# Light_Barrier_2015_3.net
KiCad netlist of a schematic drawn in EAGLE
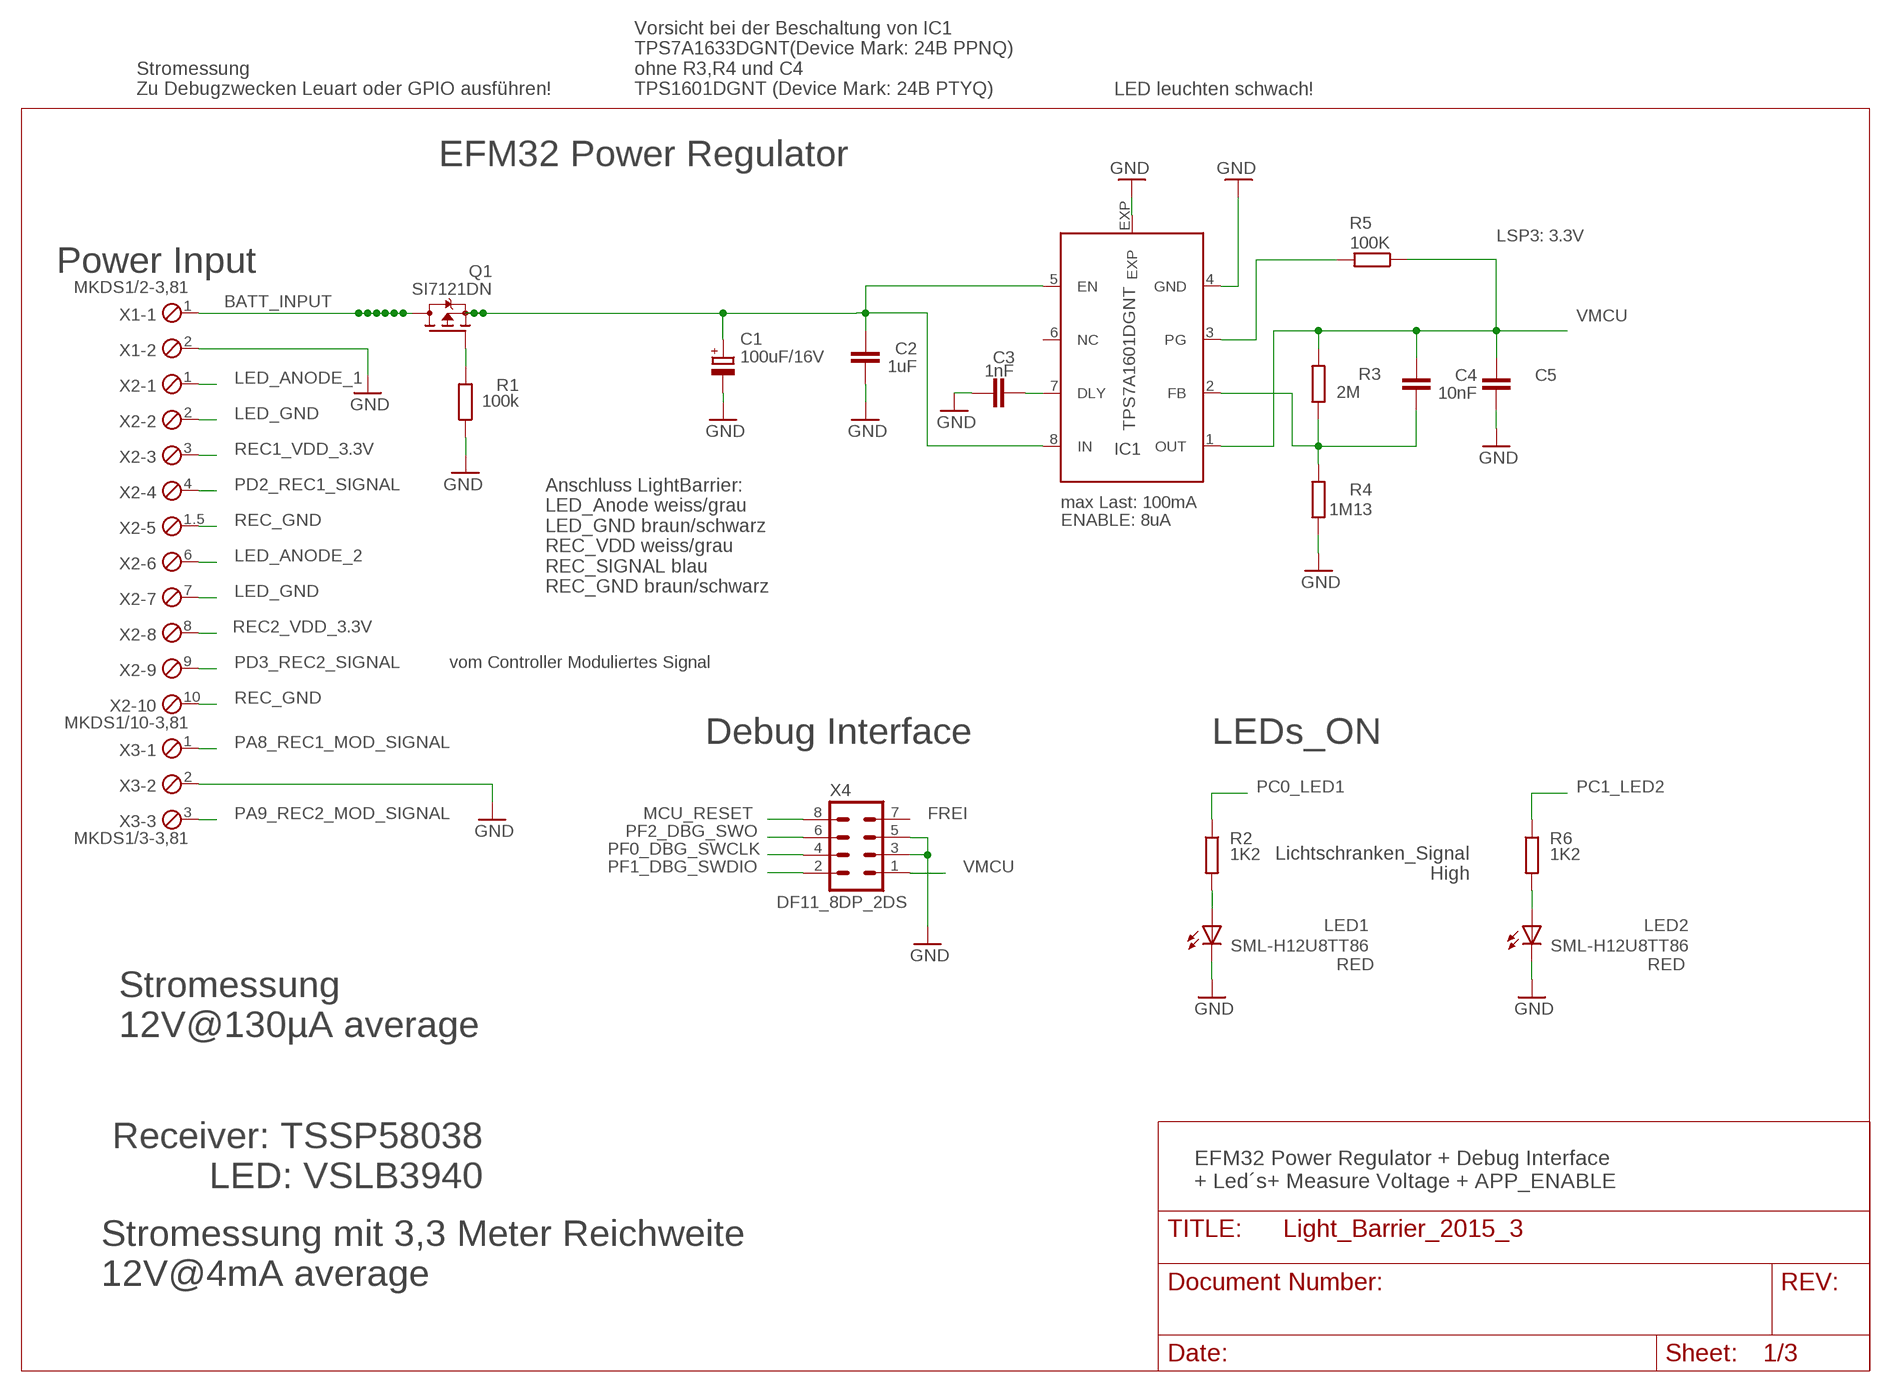
[diagram p0: schematic, sheet 1]
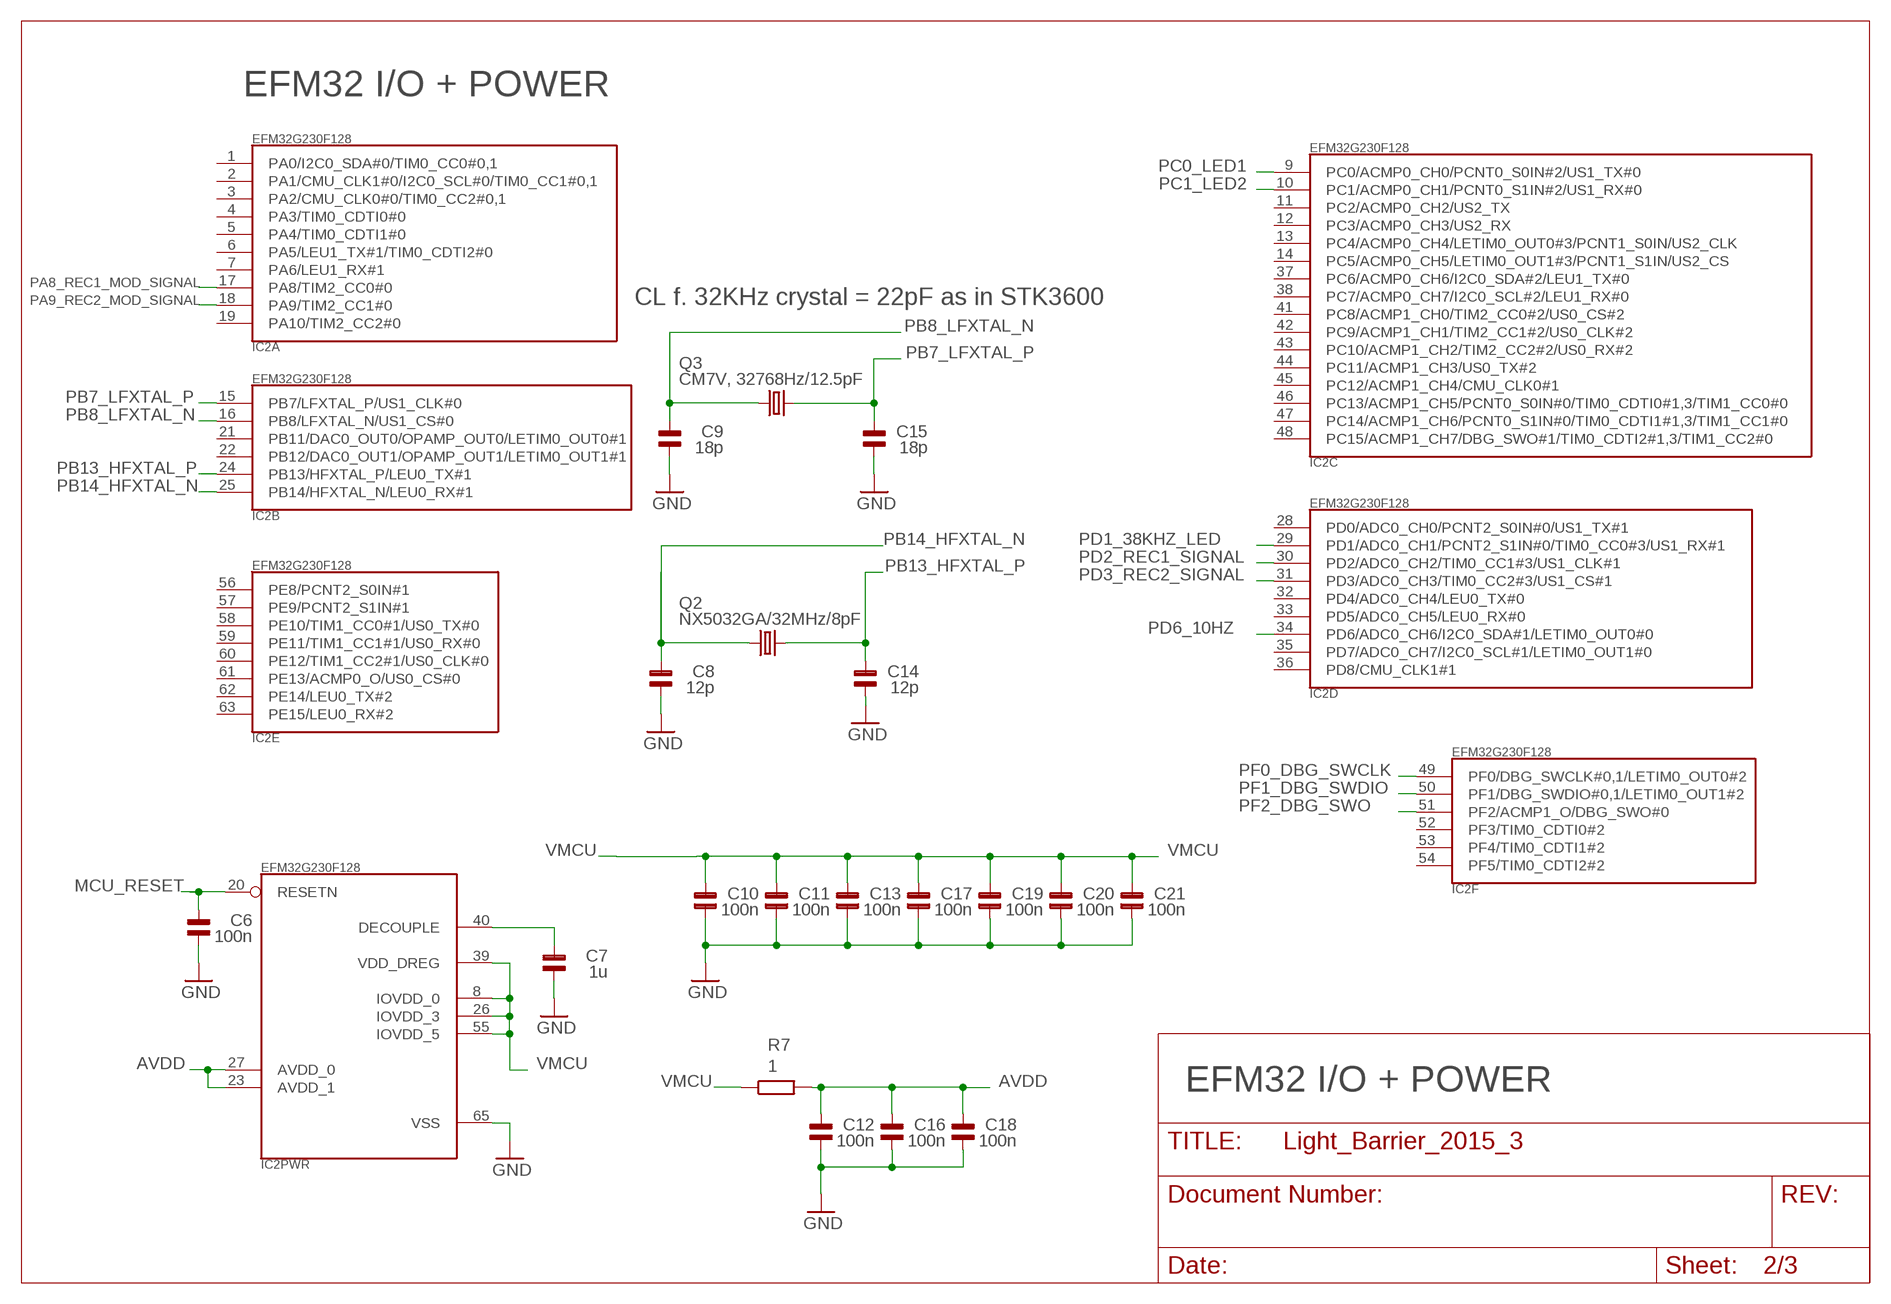
[diagram p1: schematic, sheet 2]
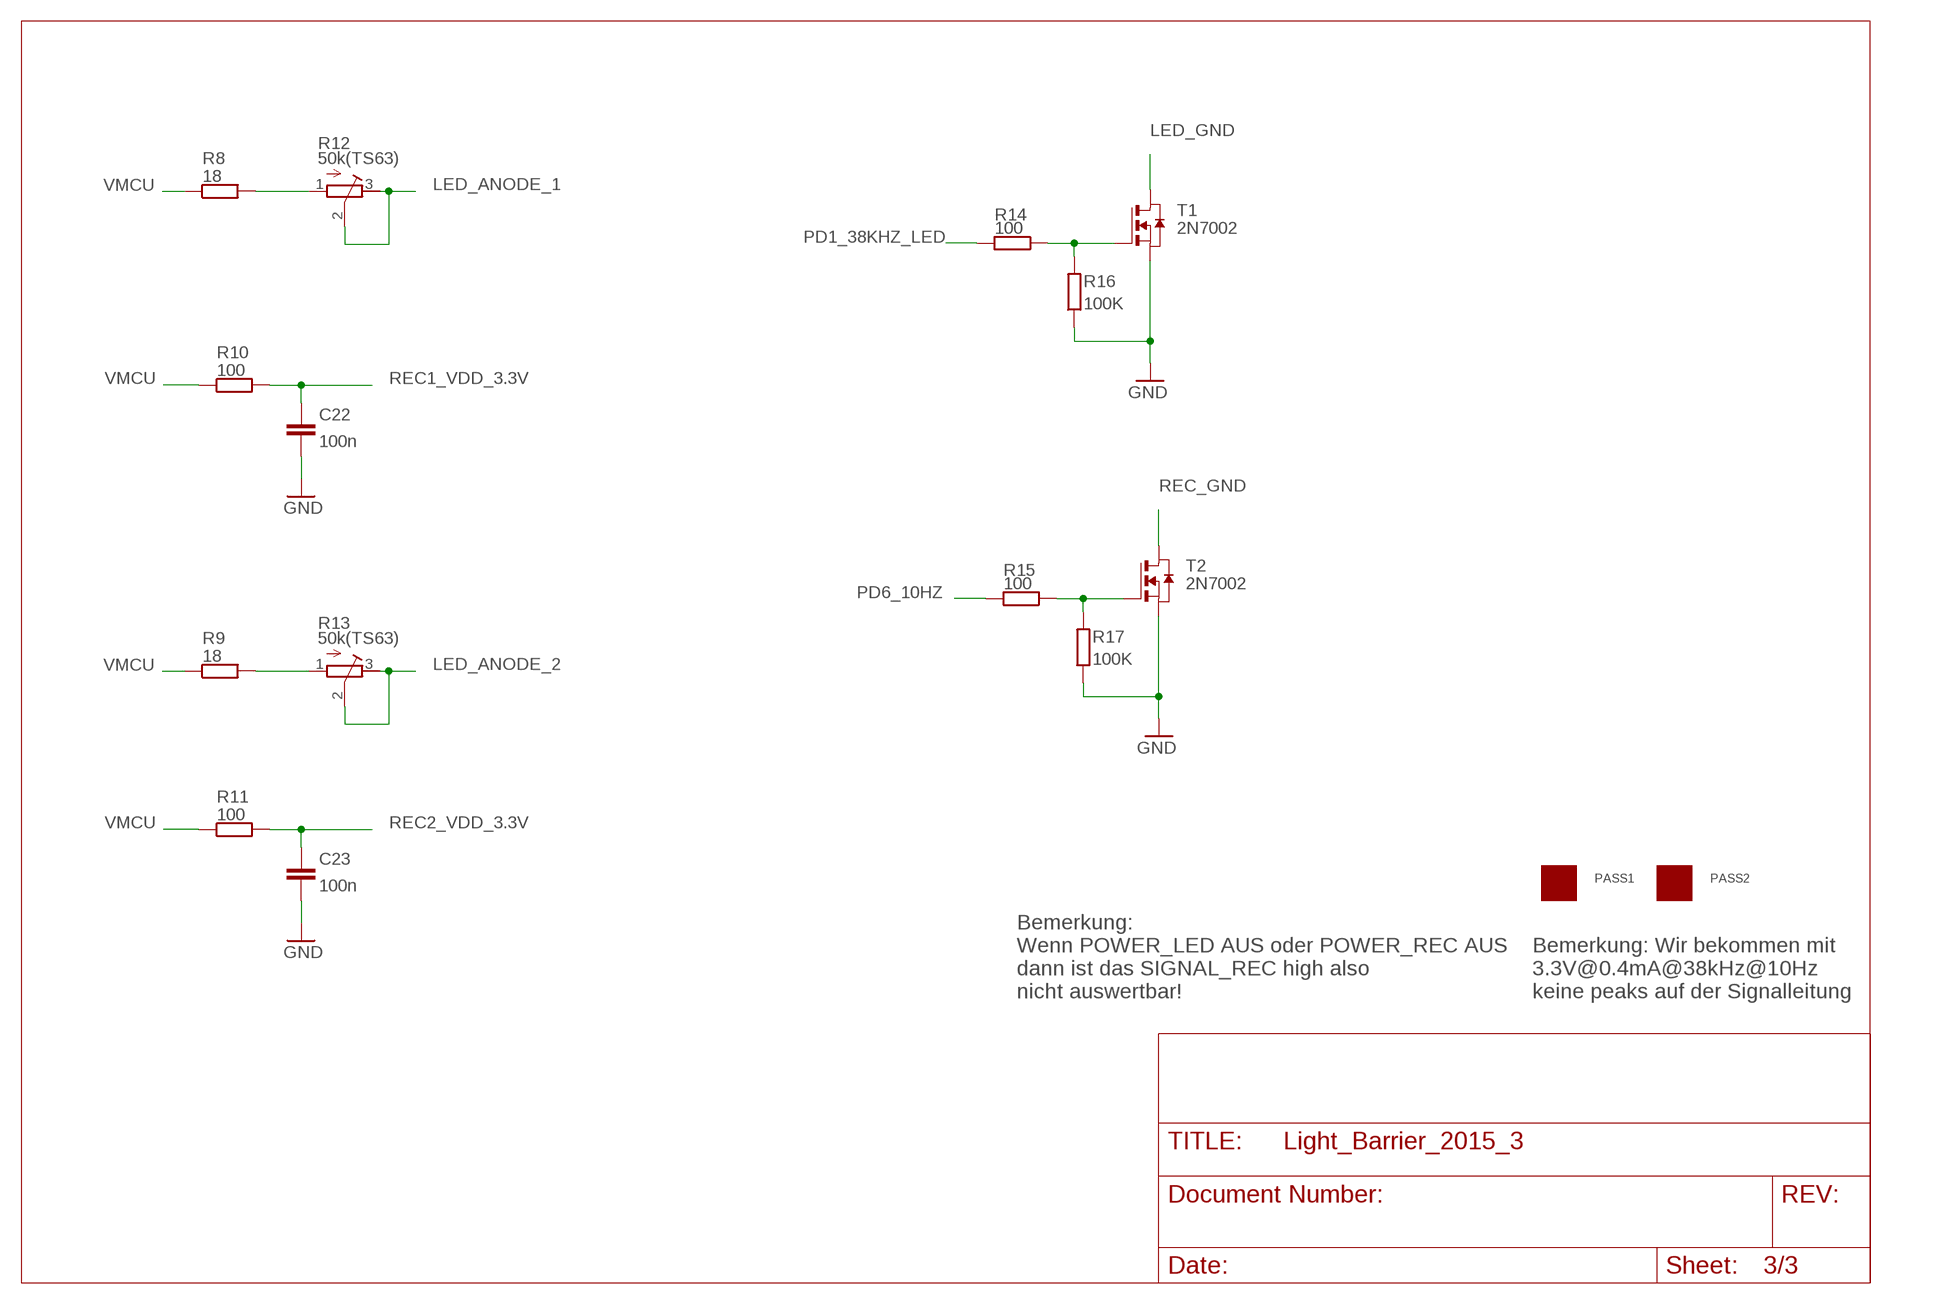
[diagram p2: schematic, sheet 3]

(export (version "E")
  (design (tool "Eeschema 10.0.6"))
  (components
    (comp (ref "C6")
      (value "100n")
      (footprint "eagle-import:0805")
      (libsource (lib "eagle-import") (part "C_SMD0805"))
    )
    (comp (ref "C7")
      (value "1u")
      (footprint "eagle-import:0805")
      (libsource (lib "eagle-import") (part "C_SMD0805"))
    )
    (comp (ref "C8")
      (value "12p")
      (footprint "eagle-import:0805")
      (libsource (lib "eagle-import") (part "C_SMD0805"))
    )
    (comp (ref "C9")
      (value "18p")
      (footprint "eagle-import:0805")
      (libsource (lib "eagle-import") (part "C_SMD0805"))
    )
    (comp (ref "C10")
      (value "100n")
      (footprint "eagle-import:0805")
      (libsource (lib "eagle-import") (part "C_SMD0805"))
    )
    (comp (ref "C11")
      (value "100n")
      (footprint "eagle-import:0805")
      (libsource (lib "eagle-import") (part "C_SMD0805"))
    )
    (comp (ref "C12")
      (value "100n")
      (footprint "eagle-import:0805")
      (libsource (lib "eagle-import") (part "C_SMD0805"))
    )
    (comp (ref "C13")
      (value "100n")
      (footprint "eagle-import:0805")
      (libsource (lib "eagle-import") (part "C_SMD0805"))
    )
    (comp (ref "C14")
      (value "12p")
      (footprint "eagle-import:0805")
      (libsource (lib "eagle-import") (part "C_SMD0805"))
    )
    (comp (ref "C15")
      (value "18p")
      (footprint "eagle-import:0805")
      (libsource (lib "eagle-import") (part "C_SMD0805"))
    )
    (comp (ref "C16")
      (value "100n")
      (footprint "eagle-import:0805")
      (libsource (lib "eagle-import") (part "C_SMD0805"))
    )
    (comp (ref "C17")
      (value "100n")
      (footprint "eagle-import:0805")
      (libsource (lib "eagle-import") (part "C_SMD0805"))
    )
    (comp (ref "C18")
      (value "100n")
      (footprint "eagle-import:0805")
      (libsource (lib "eagle-import") (part "C_SMD0805"))
    )
    (comp (ref "C19")
      (value "100n")
      (footprint "eagle-import:0805")
      (libsource (lib "eagle-import") (part "C_SMD0805"))
    )
    (comp (ref "C20")
      (value "100n")
      (footprint "eagle-import:0805")
      (libsource (lib "eagle-import") (part "C_SMD0805"))
    )
    (comp (ref "C21")
      (value "100n")
      (footprint "eagle-import:0805")
      (libsource (lib "eagle-import") (part "C_SMD0805"))
    )
    (comp (ref "IC2")
      (value "EFM32G230F128")
      (footprint "eagle-import:QFN64")
      (libsource (lib "eagle-import") (part "EFM32G230F128"))
    )
    (comp (ref "Q2")
      (value "NX5032GA/32MHz/8pF")
      (footprint "eagle-import:CRYSTAL2P5.0X3.2")
      (libsource (lib "eagle-import") (part "CRYSTAL2P5.0X3.2"))
    )
    (comp (ref "Q3")
      (value "CM7V, 32768Hz/12.5pF")
      (footprint "eagle-import:CRYSTAL2P3.2X1.5")
      (libsource (lib "eagle-import") (part "CRYSTAL2P"))
    )
    (comp (ref "R7")
      (value "1")
      (footprint "eagle-import:R0805")
      (libsource (lib "eagle-import") (part "R-EU_R0805"))
    )
    (comp (ref "C22")
      (value "100n")
      (footprint "eagle-import:C0805")
      (libsource (lib "eagle-import") (part "C-EUC0805"))
    )
    (comp (ref "C23")
      (value "100n")
      (footprint "eagle-import:C0805")
      (libsource (lib "eagle-import") (part "C-EUC0805"))
    )
    (comp (ref "PASS1")
      (value "ROUND_1MM1.5")
      (footprint "eagle-import:ROUND2_1.5MM")
      (libsource (lib "eagle-import") (part "ROUND_1MM1.5"))
    )
    (comp (ref "PASS2")
      (value "ROUND_1MM1.5")
      (footprint "eagle-import:ROUND2_1.5MM")
      (libsource (lib "eagle-import") (part "ROUND_1MM1.5"))
    )
    (comp (ref "R8")
      (value "18")
      (footprint "eagle-import:R0805")
      (libsource (lib "eagle-import") (part "R-EU_R0805"))
    )
    (comp (ref "R9")
      (value "18")
      (footprint "eagle-import:R0805")
      (libsource (lib "eagle-import") (part "R-EU_R0805"))
    )
    (comp (ref "R10")
      (value "100")
      (footprint "eagle-import:R0805")
      (libsource (lib "eagle-import") (part "R-EU_R0805"))
    )
    (comp (ref "R11")
      (value "100")
      (footprint "eagle-import:R0805")
      (libsource (lib "eagle-import") (part "R-EU_R0805"))
    )
    (comp (ref "R12")
      (value "50k(TS63)")
      (footprint "eagle-import:RTRIMTS63Y")
      (libsource (lib "eagle-import") (part "R-TRIMMTS63Y"))
    )
    (comp (ref "R13")
      (value "50k(TS63)")
      (footprint "eagle-import:RTRIMTS63Y")
      (libsource (lib "eagle-import") (part "R-TRIMMTS63Y"))
    )
    (comp (ref "R14")
      (value "100")
      (footprint "eagle-import:R0805")
      (libsource (lib "eagle-import") (part "resistor_R-EU_R0805"))
    )
    (comp (ref "R15")
      (value "100")
      (footprint "eagle-import:R0805")
      (libsource (lib "eagle-import") (part "resistor_R-EU_R0805"))
    )
    (comp (ref "R16")
      (value "100K")
      (footprint "eagle-import:R0805")
      (libsource (lib "eagle-import") (part "resistor_R-EU_R0805"))
    )
    (comp (ref "R17")
      (value "100K")
      (footprint "eagle-import:R0805")
      (libsource (lib "eagle-import") (part "resistor_R-EU_R0805"))
    )
    (comp (ref "T1")
      (value "2N7002")
      (footprint "eagle-import:ZETEX_SOT-23")
      (libsource (lib "eagle-import") (part "ZETEX_NMOSSOT23"))
    )
    (comp (ref "T2")
      (value "2N7002")
      (footprint "eagle-import:ZETEX_SOT-23")
      (libsource (lib "eagle-import") (part "ZETEX_NMOSSOT23"))
    )
    (comp (ref "C1")
      (value "100uF/16V")
      (footprint "eagle-import:PANASONIC_E")
      (libsource (lib "eagle-import") (part "CPOL-EUE"))
    )
    (comp (ref "C2")
      (value "1uF")
      (footprint "eagle-import:C0603")
      (libsource (lib "eagle-import") (part "resistor_C-EUC0603"))
    )
    (comp (ref "C3")
      (value "1nF")
      (footprint "eagle-import:C0603")
      (libsource (lib "eagle-import") (part "resistor_C-EUC0603"))
    )
    (comp (ref "C4")
      (value "10nF")
      (footprint "eagle-import:C0603")
      (libsource (lib "eagle-import") (part "resistor_C-EUC0603"))
    )
    (comp (ref "C5")
      (value "10uF")
      (footprint "eagle-import:C1206")
      (libsource (lib "eagle-import") (part "resistor_C-EUC1206"))
    )
    (comp (ref "IC1")
      (value "TPS7A1601DGNT")
      (footprint "eagle-import:DGN_S-PDSO-G8-EXP")
      (libsource (lib "eagle-import") (part "TPS7A16"))
    )
    (comp (ref "LED1")
      (value "SML-H12U8TT86")
      (footprint "eagle-import:CHIPLED_0805")
      (libsource (lib "eagle-import") (part "LEDCHIPLED_0805"))
    )
    (comp (ref "LED2")
      (value "SML-H12U8TT86")
      (footprint "eagle-import:CHIPLED_0805")
      (libsource (lib "eagle-import") (part "LEDCHIPLED_0805"))
    )
    (comp (ref "Q1")
      (value "SI7121DN")
      (footprint "eagle-import:TRANSISTOR-FET_1212-8S")
      (libsource (lib "eagle-import") (part "TRANSISTOR-FET_SI7113DN"))
    )
    (comp (ref "R1")
      (value "100k")
      (footprint "eagle-import:R0805")
      (libsource (lib "eagle-import") (part "resistor_R-EU_R0805"))
    )
    (comp (ref "R2")
      (value "1K2")
      (footprint "eagle-import:R0805")
      (libsource (lib "eagle-import") (part "resistor_R-EU_R0805"))
    )
    (comp (ref "R3")
      (value "2M")
      (footprint "eagle-import:R0805")
      (libsource (lib "eagle-import") (part "resistor_R-EU_R0805"))
    )
    (comp (ref "R4")
      (value "1M13")
      (footprint "eagle-import:R0805")
      (libsource (lib "eagle-import") (part "resistor_R-EU_R0805"))
    )
    (comp (ref "R5")
      (value "100K")
      (footprint "eagle-import:R0805")
      (libsource (lib "eagle-import") (part "resistor_R-EU_R0805"))
    )
    (comp (ref "R6")
      (value "1K2")
      (footprint "eagle-import:R0805")
      (libsource (lib "eagle-import") (part "resistor_R-EU_R0805"))
    )
    (comp (ref "X1")
      (value "MKDS1/2-3,81")
      (footprint "eagle-import:2POL381")
      (libsource (lib "eagle-import") (part "MKDS1/2-3,81"))
    )
    (comp (ref "X2")
      (value "MKDS1/10-3,81")
      (footprint "eagle-import:10POL381")
      (libsource (lib "eagle-import") (part "MKDS1/10-3,81"))
    )
    (comp (ref "X3")
      (value "MKDS1/3-3,81")
      (footprint "eagle-import:3POL381")
      (libsource (lib "eagle-import") (part "MKDS1/3-3,81"))
    )
    (comp (ref "X4")
      (value "DF11_8DP_2DS")
      (footprint "eagle-import:DP11_8DP-2DS")
      (libsource (lib "eagle-import") (part "DP11_8DP_2DS"))
    )
  )
  (nets
    (net (code "1") (name "AVDD") (class "Default")
      (node (ref "C12") (pin "2") (pinfunction "2_2") (pintype "passive"))
      (node (ref "C16") (pin "2") (pinfunction "2_2") (pintype "passive"))
      (node (ref "C18") (pin "2") (pinfunction "2_2") (pintype "passive"))
      (node (ref "IC2") (pin "23") (pinfunction "AVDD_1_23") (pintype "power_in"))
      (node (ref "IC2") (pin "27") (pinfunction "AVDD_0_27") (pintype "power_in"))
      (node (ref "R7") (pin "2") (pinfunction "2_2") (pintype "passive"))
    )
    (net (code "2") (name "BATT_INPUT") (class "Default")
      (node (ref "Q1") (pin "10") (pinfunction "D_10") (pintype "passive"))
      (node (ref "Q1") (pin "11") (pinfunction "D_11") (pintype "passive"))
      (node (ref "Q1") (pin "5") (pinfunction "D_5") (pintype "passive"))
      (node (ref "Q1") (pin "6") (pinfunction "D_6") (pintype "passive"))
      (node (ref "Q1") (pin "7") (pinfunction "D_7") (pintype "passive"))
      (node (ref "Q1") (pin "8") (pinfunction "D_8") (pintype "passive"))
      (node (ref "Q1") (pin "9") (pinfunction "D_9") (pintype "passive"))
      (node (ref "X1") (pin "1") (pinfunction "1_1") (pintype "passive"))
    )
    (net (code "3") (name "GND") (class "Default")
      (node (ref "C1") (pin "-") (pinfunction "-_-") (pintype "passive"))
      (node (ref "C10") (pin "1") (pinfunction "1_1") (pintype "passive"))
      (node (ref "C11") (pin "1") (pinfunction "1_1") (pintype "passive"))
      (node (ref "C12") (pin "1") (pinfunction "1_1") (pintype "passive"))
      (node (ref "C13") (pin "1") (pinfunction "1_1") (pintype "passive"))
      (node (ref "C14") (pin "1") (pinfunction "1_1") (pintype "passive"))
      (node (ref "C15") (pin "1") (pinfunction "1_1") (pintype "passive"))
      (node (ref "C16") (pin "1") (pinfunction "1_1") (pintype "passive"))
      (node (ref "C17") (pin "1") (pinfunction "1_1") (pintype "passive"))
      (node (ref "C18") (pin "1") (pinfunction "1_1") (pintype "passive"))
      (node (ref "C19") (pin "1") (pinfunction "1_1") (pintype "passive"))
      (node (ref "C2") (pin "1") (pinfunction "1_1") (pintype "passive"))
      (node (ref "C20") (pin "1") (pinfunction "1_1") (pintype "passive"))
      (node (ref "C21") (pin "1") (pinfunction "1_1") (pintype "passive"))
      (node (ref "C22") (pin "2") (pinfunction "2_2") (pintype "passive"))
      (node (ref "C23") (pin "2") (pinfunction "2_2") (pintype "passive"))
      (node (ref "C3") (pin "1") (pinfunction "1_1") (pintype "passive"))
      (node (ref "C5") (pin "1") (pinfunction "1_1") (pintype "passive"))
      (node (ref "C6") (pin "1") (pinfunction "1_1") (pintype "passive"))
      (node (ref "C7") (pin "1") (pinfunction "1_1") (pintype "passive"))
      (node (ref "C8") (pin "1") (pinfunction "1_1") (pintype "passive"))
      (node (ref "C9") (pin "1") (pinfunction "1_1") (pintype "passive"))
      (node (ref "IC1") (pin "4") (pinfunction "GND_4") (pintype "passive"))
      (node (ref "IC1") (pin "EXP") (pinfunction "EXP_EXP") (pintype "passive"))
      (node (ref "IC2") (pin "65") (pinfunction "VSS_65") (pintype "power_in"))
      (node (ref "LED1") (pin "C") (pinfunction "C_C") (pintype "passive"))
      (node (ref "LED2") (pin "C") (pinfunction "C_C") (pintype "passive"))
      (node (ref "R1") (pin "1") (pinfunction "1_1") (pintype "passive"))
      (node (ref "R16") (pin "1") (pinfunction "1_1") (pintype "passive"))
      (node (ref "R17") (pin "1") (pinfunction "1_1") (pintype "passive"))
      (node (ref "R4") (pin "1") (pinfunction "1_1") (pintype "passive"))
      (node (ref "T1") (pin "2") (pinfunction "S_2") (pintype "passive"))
      (node (ref "T2") (pin "2") (pinfunction "S_2") (pintype "passive"))
      (node (ref "X1") (pin "2") (pinfunction "1_2") (pintype "passive"))
      (node (ref "X3") (pin "2") (pinfunction "1_2") (pintype "passive"))
      (node (ref "X4") (pin "3") (pinfunction "3_3") (pintype "passive"))
      (node (ref "X4") (pin "5") (pinfunction "5_5") (pintype "passive"))
    )
    (net (code "4") (name "LED_ANODE_1") (class "Default")
      (node (ref "R12") (pin "2") (pinfunction "S_2") (pintype "passive"))
      (node (ref "R12") (pin "3") (pinfunction "E_3") (pintype "passive"))
      (node (ref "X2") (pin "1") (pinfunction "1_1") (pintype "passive"))
    )
    (net (code "5") (name "LED_ANODE_2") (class "Default")
      (node (ref "R13") (pin "2") (pinfunction "S_2") (pintype "passive"))
      (node (ref "R13") (pin "3") (pinfunction "E_3") (pintype "passive"))
      (node (ref "X2") (pin "6") (pinfunction "1_6") (pintype "passive"))
    )
    (net (code "6") (name "LED_GND") (class "Default")
      (node (ref "T1") (pin "1") (pinfunction "D_1") (pintype "passive"))
      (node (ref "X2") (pin "2") (pinfunction "1_2") (pintype "passive"))
      (node (ref "X2") (pin "7") (pinfunction "1_7") (pintype "passive"))
    )
    (net (code "7") (name "MCU_RESET") (class "Default")
      (node (ref "C6") (pin "2") (pinfunction "2_2") (pintype "passive"))
      (node (ref "IC2") (pin "20") (pinfunction "RESETN_20") (pintype "passive"))
      (node (ref "X4") (pin "8") (pinfunction "8_8") (pintype "passive"))
    )
    (net (code "8") (name "Net-(IC1-DLY)") (class "Default")
      (node (ref "C3") (pin "2") (pinfunction "2_2") (pintype "passive"))
      (node (ref "IC1") (pin "7") (pinfunction "DLY_7") (pintype "output"))
    )
    (net (code "9") (name "Net-(IC1-EN)") (class "Default")
      (node (ref "C1") (pin "+") (pinfunction "+_+") (pintype "passive"))
      (node (ref "C2") (pin "2") (pinfunction "2_2") (pintype "passive"))
      (node (ref "IC1") (pin "5") (pinfunction "EN_5") (pintype "input"))
      (node (ref "IC1") (pin "8") (pinfunction "IN_8") (pintype "passive"))
      (node (ref "Q1") (pin "1") (pinfunction "S_1") (pintype "passive"))
      (node (ref "Q1") (pin "2") (pinfunction "S_2") (pintype "passive"))
      (node (ref "Q1") (pin "3") (pinfunction "S_3") (pintype "passive"))
    )
    (net (code "10") (name "Net-(IC1-FB)") (class "Default")
      (node (ref "C4") (pin "1") (pinfunction "1_1") (pintype "passive"))
      (node (ref "IC1") (pin "2") (pinfunction "FB_2") (pintype "input"))
      (node (ref "R3") (pin "1") (pinfunction "1_1") (pintype "passive"))
      (node (ref "R4") (pin "2") (pinfunction "2_2") (pintype "passive"))
    )
    (net (code "11") (name "Net-(IC1-PG)") (class "Default")
      (node (ref "IC1") (pin "3") (pinfunction "PG_3") (pintype "output"))
      (node (ref "R5") (pin "2") (pinfunction "2_2") (pintype "passive"))
    )
    (net (code "12") (name "Net-(IC2G-DECOUPLE)") (class "Default")
      (node (ref "C7") (pin "2") (pinfunction "2_2") (pintype "passive"))
      (node (ref "IC2") (pin "40") (pinfunction "DECOUPLE_40") (pintype "power_in"))
    )
    (net (code "13") (name "Net-(LED1-PadA)") (class "Default")
      (node (ref "LED1") (pin "A") (pinfunction "A_A") (pintype "passive"))
      (node (ref "R2") (pin "2") (pinfunction "2_2") (pintype "passive"))
    )
    (net (code "14") (name "Net-(LED2-PadA)") (class "Default")
      (node (ref "LED2") (pin "A") (pinfunction "A_A") (pintype "passive"))
      (node (ref "R6") (pin "2") (pinfunction "2_2") (pintype "passive"))
    )
    (net (code "15") (name "Net-(Q1-G)") (class "Default")
      (node (ref "Q1") (pin "4") (pinfunction "G_4") (pintype "passive"))
      (node (ref "R1") (pin "2") (pinfunction "2_2") (pintype "passive"))
    )
    (net (code "16") (name "Net-(R12-A)") (class "Default")
      (node (ref "R12") (pin "1") (pinfunction "A_1") (pintype "passive"))
      (node (ref "R8") (pin "2") (pinfunction "2_2") (pintype "passive"))
    )
    (net (code "17") (name "Net-(R13-A)") (class "Default")
      (node (ref "R13") (pin "1") (pinfunction "A_1") (pintype "passive"))
      (node (ref "R9") (pin "2") (pinfunction "2_2") (pintype "passive"))
    )
    (net (code "18") (name "Net-(T1-G)") (class "Default")
      (node (ref "R14") (pin "1") (pinfunction "1_1") (pintype "passive"))
      (node (ref "R16") (pin "2") (pinfunction "2_2") (pintype "passive"))
      (node (ref "T1") (pin "3") (pinfunction "G_3") (pintype "passive"))
    )
    (net (code "19") (name "Net-(T2-G)") (class "Default")
      (node (ref "R15") (pin "1") (pinfunction "1_1") (pintype "passive"))
      (node (ref "R17") (pin "2") (pinfunction "2_2") (pintype "passive"))
      (node (ref "T2") (pin "3") (pinfunction "G_3") (pintype "passive"))
    )
    (net (code "20") (name "PA8_REC1_MOD_SIGNAL") (class "Default")
      (node (ref "IC2") (pin "17") (pinfunction "PA8/TIM2_CC0#0_17") (pintype "bidirectional"))
      (node (ref "X3") (pin "1") (pinfunction "1_1") (pintype "passive"))
    )
    (net (code "21") (name "PA9_REC2_MOD_SIGNAL") (class "Default")
      (node (ref "IC2") (pin "18") (pinfunction "PA9/TIM2_CC1#0_18") (pintype "bidirectional"))
      (node (ref "X3") (pin "3") (pinfunction "1_3") (pintype "passive"))
    )
    (net (code "22") (name "PB7_LFXTAL_P") (class "Default")
      (node (ref "C15") (pin "2") (pinfunction "2_2") (pintype "passive"))
      (node (ref "IC2") (pin "15") (pinfunction "PB7/LFXTAL_P/US1_CLK#0_15") (pintype "bidirectional"))
      (node (ref "Q3") (pin "2") (pinfunction "2_2") (pintype "passive"))
    )
    (net (code "23") (name "PB8_LFXTAL_N") (class "Default")
      (node (ref "C9") (pin "2") (pinfunction "2_2") (pintype "passive"))
      (node (ref "IC2") (pin "16") (pinfunction "PB8/LFXTAL_N/US1_CS#0_16") (pintype "bidirectional"))
      (node (ref "Q3") (pin "1") (pinfunction "1_1") (pintype "passive"))
    )
    (net (code "24") (name "PB13_HFXTAL_P") (class "Default")
      (node (ref "C14") (pin "2") (pinfunction "2_2") (pintype "passive"))
      (node (ref "IC2") (pin "24") (pinfunction "PB13/HFXTAL_P/LEU0_TX#1_24") (pintype "bidirectional"))
      (node (ref "Q2") (pin "2") (pinfunction "2_2") (pintype "passive"))
    )
    (net (code "25") (name "PB14_HFXTAL_N") (class "Default")
      (node (ref "C8") (pin "2") (pinfunction "2_2") (pintype "passive"))
      (node (ref "IC2") (pin "25") (pinfunction "PB14/HFXTAL_N/LEU0_RX#1_25") (pintype "bidirectional"))
      (node (ref "Q2") (pin "1") (pinfunction "1_1") (pintype "passive"))
    )
    (net (code "26") (name "PC0_LED1") (class "Default")
      (node (ref "IC2") (pin "9") (pinfunction "PC0/ACMP0_CH0/PCNT0_S0IN#2/US1_TX#0_9") (pintype "bidirectional"))
      (node (ref "R2") (pin "1") (pinfunction "1_1") (pintype "passive"))
    )
    (net (code "27") (name "PC1_LED2") (class "Default")
      (node (ref "IC2") (pin "10") (pinfunction "PC1/ACMP0_CH1/PCNT0_S1IN#2/US1_RX#0_10") (pintype "bidirectional"))
      (node (ref "R6") (pin "1") (pinfunction "1_1") (pintype "passive"))
    )
    (net (code "28") (name "PD1_38KHZ_LED") (class "Default")
      (node (ref "IC2") (pin "29") (pinfunction "PD1/ADC0_CH1/PCNT2_S1IN#0/TIM0_CC0#3/US1_RX#1_29") (pintype "bidirectional"))
      (node (ref "R14") (pin "2") (pinfunction "2_2") (pintype "passive"))
    )
    (net (code "29") (name "PD2_REC1_SIGNAL") (class "Default")
      (node (ref "IC2") (pin "30") (pinfunction "PD2/ADC0_CH2/TIM0_CC1#3/US1_CLK#1_30") (pintype "bidirectional"))
      (node (ref "X2") (pin "4") (pinfunction "1_4") (pintype "passive"))
    )
    (net (code "30") (name "PD3_REC2_SIGNAL") (class "Default")
      (node (ref "IC2") (pin "31") (pinfunction "PD3/ADC0_CH3/TIM0_CC2#3/US1_CS#1_31") (pintype "bidirectional"))
      (node (ref "X2") (pin "9") (pinfunction "1_9") (pintype "passive"))
    )
    (net (code "31") (name "PD6_10HZ") (class "Default")
      (node (ref "IC2") (pin "34") (pinfunction "PD6/ADC0_CH6/I2C0_SDA#1/LETIM0_OUT0#0_34") (pintype "bidirectional"))
      (node (ref "R15") (pin "2") (pinfunction "2_2") (pintype "passive"))
    )
    (net (code "32") (name "PF0_DBG_SWCLK") (class "Default")
      (node (ref "IC2") (pin "49") (pinfunction "PF0/DBG_SWCLK#0,1/LETIM0_OUT0#2_49") (pintype "bidirectional"))
      (node (ref "X4") (pin "4") (pinfunction "4_4") (pintype "passive"))
    )
    (net (code "33") (name "PF1_DBG_SWDIO") (class "Default")
      (node (ref "IC2") (pin "50") (pinfunction "PF1/DBG_SWDIO#0,1/LETIM0_OUT1#2_50") (pintype "bidirectional"))
      (node (ref "X4") (pin "2") (pinfunction "2_2") (pintype "passive"))
    )
    (net (code "34") (name "PF2_DBG_SWO") (class "Default")
      (node (ref "IC2") (pin "51") (pinfunction "PF2/ACMP1_O/DBG_SWO#0_51") (pintype "bidirectional"))
      (node (ref "X4") (pin "6") (pinfunction "6_6") (pintype "passive"))
    )
    (net (code "35") (name "REC1_VDD_3.3V") (class "Default")
      (node (ref "C22") (pin "1") (pinfunction "1_1") (pintype "passive"))
      (node (ref "R10") (pin "2") (pinfunction "2_2") (pintype "passive"))
      (node (ref "X2") (pin "3") (pinfunction "1_3") (pintype "passive"))
    )
    (net (code "36") (name "REC2_VDD_3.3V") (class "Default")
      (node (ref "C23") (pin "1") (pinfunction "1_1") (pintype "passive"))
      (node (ref "R11") (pin "2") (pinfunction "2_2") (pintype "passive"))
      (node (ref "X2") (pin "8") (pinfunction "1_8") (pintype "passive"))
    )
    (net (code "37") (name "REC_GND") (class "Default")
      (node (ref "T2") (pin "1") (pinfunction "D_1") (pintype "passive"))
      (node (ref "X2") (pin "1.5") (pinfunction "1_1.5") (pintype "passive"))
      (node (ref "X2") (pin "10") (pinfunction "1_10") (pintype "passive"))
    )
    (net (code "38") (name "VMCU") (class "Default")
      (node (ref "C10") (pin "2") (pinfunction "2_2") (pintype "passive"))
      (node (ref "C11") (pin "2") (pinfunction "2_2") (pintype "passive"))
      (node (ref "C13") (pin "2") (pinfunction "2_2") (pintype "passive"))
      (node (ref "C17") (pin "2") (pinfunction "2_2") (pintype "passive"))
      (node (ref "C19") (pin "2") (pinfunction "2_2") (pintype "passive"))
      (node (ref "C20") (pin "2") (pinfunction "2_2") (pintype "passive"))
      (node (ref "C21") (pin "2") (pinfunction "2_2") (pintype "passive"))
      (node (ref "C4") (pin "2") (pinfunction "2_2") (pintype "passive"))
      (node (ref "C5") (pin "2") (pinfunction "2_2") (pintype "passive"))
      (node (ref "IC1") (pin "1") (pinfunction "OUT_1") (pintype "output"))
      (node (ref "IC2") (pin "26") (pinfunction "IOVDD_3_26") (pintype "power_in"))
      (node (ref "IC2") (pin "39") (pinfunction "VDD_DREG_39") (pintype "power_in"))
      (node (ref "IC2") (pin "55") (pinfunction "IOVDD_5_55") (pintype "power_in"))
      (node (ref "IC2") (pin "8") (pinfunction "IOVDD_0_8") (pintype "power_in"))
      (node (ref "R10") (pin "1") (pinfunction "1_1") (pintype "passive"))
      (node (ref "R11") (pin "1") (pinfunction "1_1") (pintype "passive"))
      (node (ref "R3") (pin "2") (pinfunction "2_2") (pintype "passive"))
      (node (ref "R5") (pin "1") (pinfunction "1_1") (pintype "passive"))
      (node (ref "R7") (pin "1") (pinfunction "1_1") (pintype "passive"))
      (node (ref "R8") (pin "1") (pinfunction "1_1") (pintype "passive"))
      (node (ref "R9") (pin "1") (pinfunction "1_1") (pintype "passive"))
      (node (ref "X4") (pin "1") (pinfunction "1_1") (pintype "passive"))
    )
    (net (code "39") (name "unconnected-(IC1-NC-Pad6)") (class "Default")
      (node (ref "IC1") (pin "6") (pinfunction "NC_6") (pintype "no_connect"))
    )
    (net (code "40") (name "unconnected-(IC2A-PA0{slash}I2C0_SDA#0{slash}TIM0_CC0#0,1-Pad1)") (class "Default")
      (node (ref "IC2") (pin "1") (pinfunction "PA0/I2C0_SDA#0/TIM0_CC0#0,1_1") (pintype "bidirectional"))
    )
    (net (code "41") (name "unconnected-(IC2A-PA1{slash}CMU_CLK1#0{slash}I2C0_SCL#0{slash}TIM0_CC1#0,1-Pad2)") (class "Default")
      (node (ref "IC2") (pin "2") (pinfunction "PA1/CMU_CLK1#0/I2C0_SCL#0/TIM0_CC1#0,1_2") (pintype "bidirectional"))
    )
    (net (code "42") (name "unconnected-(IC2A-PA2{slash}CMU_CLK0#0{slash}TIM0_CC2#0,1-Pad3)") (class "Default")
      (node (ref "IC2") (pin "3") (pinfunction "PA2/CMU_CLK0#0/TIM0_CC2#0,1_3") (pintype "bidirectional"))
    )
    (net (code "43") (name "unconnected-(IC2A-PA3{slash}TIM0_CDTI0#0-Pad4)") (class "Default")
      (node (ref "IC2") (pin "4") (pinfunction "PA3/TIM0_CDTI0#0_4") (pintype "bidirectional"))
    )
    (net (code "44") (name "unconnected-(IC2A-PA4{slash}TIM0_CDTI1#0-Pad5)") (class "Default")
      (node (ref "IC2") (pin "5") (pinfunction "PA4/TIM0_CDTI1#0_5") (pintype "bidirectional"))
    )
    (net (code "45") (name "unconnected-(IC2A-PA5{slash}LEU1_TX#1{slash}TIM0_CDTI2#0-Pad6)") (class "Default")
      (node (ref "IC2") (pin "6") (pinfunction "PA5/LEU1_TX#1/TIM0_CDTI2#0_6") (pintype "bidirectional"))
    )
    (net (code "46") (name "unconnected-(IC2A-PA6{slash}LEU1_RX#1-Pad7)") (class "Default")
      (node (ref "IC2") (pin "7") (pinfunction "PA6/LEU1_RX#1_7") (pintype "bidirectional"))
    )
    (net (code "47") (name "unconnected-(IC2A-PA10{slash}TIM2_CC2#0-Pad19)") (class "Default")
      (node (ref "IC2") (pin "19") (pinfunction "PA10/TIM2_CC2#0_19") (pintype "bidirectional"))
    )
    (net (code "48") (name "unconnected-(IC2B-PB11{slash}DAC0_OUT0{slash}OPAMP_OUT0{slash}LETIM0_OUT0#1-Pad21)") (class "Default")
      (node (ref "IC2") (pin "21") (pinfunction "PB11/DAC0_OUT0/OPAMP_OUT0/LETIM0_OUT0#1_21") (pintype "bidirectional"))
    )
    (net (code "49") (name "unconnected-(IC2B-PB12{slash}DAC0_OUT1{slash}OPAMP_OUT1{slash}LETIM0_OUT1#1-Pad22)") (class "Default")
      (node (ref "IC2") (pin "22") (pinfunction "PB12/DAC0_OUT1/OPAMP_OUT1/LETIM0_OUT1#1_22") (pintype "bidirectional"))
    )
    (net (code "50") (name "unconnected-(IC2C-PC2{slash}ACMP0_CH2{slash}US2_TX-Pad11)") (class "Default")
      (node (ref "IC2") (pin "11") (pinfunction "PC2/ACMP0_CH2/US2_TX_11") (pintype "bidirectional"))
    )
    (net (code "51") (name "unconnected-(IC2C-PC3{slash}ACMP0_CH3{slash}US2_RX-Pad12)") (class "Default")
      (node (ref "IC2") (pin "12") (pinfunction "PC3/ACMP0_CH3/US2_RX_12") (pintype "bidirectional"))
    )
    (net (code "52") (name "unconnected-(IC2C-PC4{slash}ACMP0_CH4{slash}LETIM0_OUT0#3{slash}PCNT1_S0IN{slash}US2_CLK-Pad13)") (class "Default")
      (node (ref "IC2") (pin "13") (pinfunction "PC4/ACMP0_CH4/LETIM0_OUT0#3/PCNT1_S0IN/US2_CLK_13") (pintype "bidirectional"))
    )
    (net (code "53") (name "unconnected-(IC2C-PC5{slash}ACMP0_CH5{slash}LETIM0_OUT1#3{slash}PCNT1_S1IN{slash}US2_CS-Pad14)") (class "Default")
      (node (ref "IC2") (pin "14") (pinfunction "PC5/ACMP0_CH5/LETIM0_OUT1#3/PCNT1_S1IN/US2_CS_14") (pintype "bidirectional"))
    )
    (net (code "54") (name "unconnected-(IC2C-PC6{slash}ACMP0_CH6{slash}I2C0_SDA#2{slash}LEU1_TX#0-Pad37)") (class "Default")
      (node (ref "IC2") (pin "37") (pinfunction "PC6/ACMP0_CH6/I2C0_SDA#2/LEU1_TX#0_37") (pintype "bidirectional"))
    )
    (net (code "55") (name "unconnected-(IC2C-PC7{slash}ACMP0_CH7{slash}I2C0_SCL#2{slash}LEU1_RX#0-Pad38)") (class "Default")
      (node (ref "IC2") (pin "38") (pinfunction "PC7/ACMP0_CH7/I2C0_SCL#2/LEU1_RX#0_38") (pintype "bidirectional"))
    )
    (net (code "56") (name "unconnected-(IC2C-PC8{slash}ACMP1_CH0{slash}TIM2_CC0#2{slash}US0_CS#2-Pad41)") (class "Default")
      (node (ref "IC2") (pin "41") (pinfunction "PC8/ACMP1_CH0/TIM2_CC0#2/US0_CS#2_41") (pintype "bidirectional"))
    )
    (net (code "57") (name "unconnected-(IC2C-PC9{slash}ACMP1_CH1{slash}TIM2_CC1#2{slash}US0_CLK#2-Pad42)") (class "Default")
      (node (ref "IC2") (pin "42") (pinfunction "PC9/ACMP1_CH1/TIM2_CC1#2/US0_CLK#2_42") (pintype "bidirectional"))
    )
    (net (code "58") (name "unconnected-(IC2C-PC10{slash}ACMP1_CH2{slash}TIM2_CC2#2{slash}US0_RX#2-Pad43)") (class "Default")
      (node (ref "IC2") (pin "43") (pinfunction "PC10/ACMP1_CH2/TIM2_CC2#2/US0_RX#2_43") (pintype "bidirectional"))
    )
    (net (code "59") (name "unconnected-(IC2C-PC11{slash}ACMP1_CH3{slash}US0_TX#2-Pad44)") (class "Default")
      (node (ref "IC2") (pin "44") (pinfunction "PC11/ACMP1_CH3/US0_TX#2_44") (pintype "bidirectional"))
    )
    (net (code "60") (name "unconnected-(IC2C-PC12{slash}ACMP1_CH4{slash}CMU_CLK0#1-Pad45)") (class "Default")
      (node (ref "IC2") (pin "45") (pinfunction "PC12/ACMP1_CH4/CMU_CLK0#1_45") (pintype "bidirectional"))
    )
    (net (code "61") (name "unconnected-(IC2C-PC13{slash}ACMP1_CH5{slash}PCNT0_S0IN#0{slash}TIM0_CDTI0#1,3{slash}TIM1_CC0#0-Pad46)") (class "Default")
      (node (ref "IC2") (pin "46") (pinfunction "PC13/ACMP1_CH5/PCNT0_S0IN#0/TIM0_CDTI0#1,3/TIM1_CC0#0_46") (pintype "bidirectional"))
    )
    (net (code "62") (name "unconnected-(IC2C-PC14{slash}ACMP1_CH6{slash}PCNT0_S1IN#0{slash}TIM0_CDTI1#1,3{slash}TIM1_CC1#0-Pad47)") (class "Default")
      (node (ref "IC2") (pin "47") (pinfunction "PC14/ACMP1_CH6/PCNT0_S1IN#0/TIM0_CDTI1#1,3/TIM1_CC1#0_47") (pintype "bidirectional"))
    )
    (net (code "63") (name "unconnected-(IC2C-PC15{slash}ACMP1_CH7{slash}DBG_SWO#1{slash}TIM0_CDTI2#1,3{slash}TIM1_CC2#0-Pad48)") (class "Default")
      (node (ref "IC2") (pin "48") (pinfunction "PC15/ACMP1_CH7/DBG_SWO#1/TIM0_CDTI2#1,3/TIM1_CC2#0_48") (pintype "bidirectional"))
    )
    (net (code "64") (name "unconnected-(IC2D-PD0{slash}ADC0_CH0{slash}PCNT2_S0IN#0{slash}US1_TX#1-Pad28)") (class "Default")
      (node (ref "IC2") (pin "28") (pinfunction "PD0/ADC0_CH0/PCNT2_S0IN#0/US1_TX#1_28") (pintype "bidirectional"))
    )
    (net (code "65") (name "unconnected-(IC2D-PD4{slash}ADC0_CH4{slash}LEU0_TX#0-Pad32)") (class "Default")
      (node (ref "IC2") (pin "32") (pinfunction "PD4/ADC0_CH4/LEU0_TX#0_32") (pintype "bidirectional"))
    )
    (net (code "66") (name "unconnected-(IC2D-PD5{slash}ADC0_CH5{slash}LEU0_RX#0-Pad33)") (class "Default")
      (node (ref "IC2") (pin "33") (pinfunction "PD5/ADC0_CH5/LEU0_RX#0_33") (pintype "bidirectional"))
    )
    (net (code "67") (name "unconnected-(IC2D-PD7{slash}ADC0_CH7{slash}I2C0_SCL#1{slash}LETIM0_OUT1#0-Pad35)") (class "Default")
      (node (ref "IC2") (pin "35") (pinfunction "PD7/ADC0_CH7/I2C0_SCL#1/LETIM0_OUT1#0_35") (pintype "bidirectional"))
    )
    (net (code "68") (name "unconnected-(IC2D-PD8{slash}CMU_CLK1#1-Pad36)") (class "Default")
      (node (ref "IC2") (pin "36") (pinfunction "PD8/CMU_CLK1#1_36") (pintype "bidirectional"))
    )
    (net (code "69") (name "unconnected-(IC2E-PE8{slash}PCNT2_S0IN#1-Pad56)") (class "Default")
      (node (ref "IC2") (pin "56") (pinfunction "PE8/PCNT2_S0IN#1_56") (pintype "bidirectional"))
    )
    (net (code "70") (name "unconnected-(IC2E-PE9{slash}PCNT2_S1IN#1-Pad57)") (class "Default")
      (node (ref "IC2") (pin "57") (pinfunction "PE9/PCNT2_S1IN#1_57") (pintype "bidirectional"))
    )
    (net (code "71") (name "unconnected-(IC2E-PE10{slash}TIM1_CC0#1{slash}US0_TX#0-Pad58)") (class "Default")
      (node (ref "IC2") (pin "58") (pinfunction "PE10/TIM1_CC0#1/US0_TX#0_58") (pintype "bidirectional"))
    )
    (net (code "72") (name "unconnected-(IC2E-PE11{slash}TIM1_CC1#1{slash}US0_RX#0-Pad59)") (class "Default")
      (node (ref "IC2") (pin "59") (pinfunction "PE11/TIM1_CC1#1/US0_RX#0_59") (pintype "bidirectional"))
    )
    (net (code "73") (name "unconnected-(IC2E-PE12{slash}TIM1_CC2#1{slash}US0_CLK#0-Pad60)") (class "Default")
      (node (ref "IC2") (pin "60") (pinfunction "PE12/TIM1_CC2#1/US0_CLK#0_60") (pintype "bidirectional"))
    )
    (net (code "74") (name "unconnected-(IC2E-PE13{slash}ACMP0_O{slash}US0_CS#0-Pad61)") (class "Default")
      (node (ref "IC2") (pin "61") (pinfunction "PE13/ACMP0_O/US0_CS#0_61") (pintype "bidirectional"))
    )
    (net (code "75") (name "unconnected-(IC2E-PE14{slash}LEU0_TX#2-Pad62)") (class "Default")
      (node (ref "IC2") (pin "62") (pinfunction "PE14/LEU0_TX#2_62") (pintype "bidirectional"))
    )
    (net (code "76") (name "unconnected-(IC2E-PE15{slash}LEU0_RX#2-Pad63)") (class "Default")
      (node (ref "IC2") (pin "63") (pinfunction "PE15/LEU0_RX#2_63") (pintype "bidirectional"))
    )
    (net (code "77") (name "unconnected-(IC2F-PF3{slash}TIM0_CDTI0#2-Pad52)") (class "Default")
      (node (ref "IC2") (pin "52") (pinfunction "PF3/TIM0_CDTI0#2_52") (pintype "bidirectional"))
    )
    (net (code "78") (name "unconnected-(IC2F-PF4{slash}TIM0_CDTI1#2-Pad53)") (class "Default")
      (node (ref "IC2") (pin "53") (pinfunction "PF4/TIM0_CDTI1#2_53") (pintype "bidirectional"))
    )
    (net (code "79") (name "unconnected-(IC2F-PF5{slash}TIM0_CDTI2#2-Pad54)") (class "Default")
      (node (ref "IC2") (pin "54") (pinfunction "PF5/TIM0_CDTI2#2_54") (pintype "bidirectional"))
    )
    (net (code "80") (name "unconnected-(X4-Pad7)") (class "Default")
      (node (ref "X4") (pin "7") (pinfunction "7_7") (pintype "passive"))
    )
  )
)
